# V3_nano.net
KiCad netlist of a schematic drawn in EAGLE
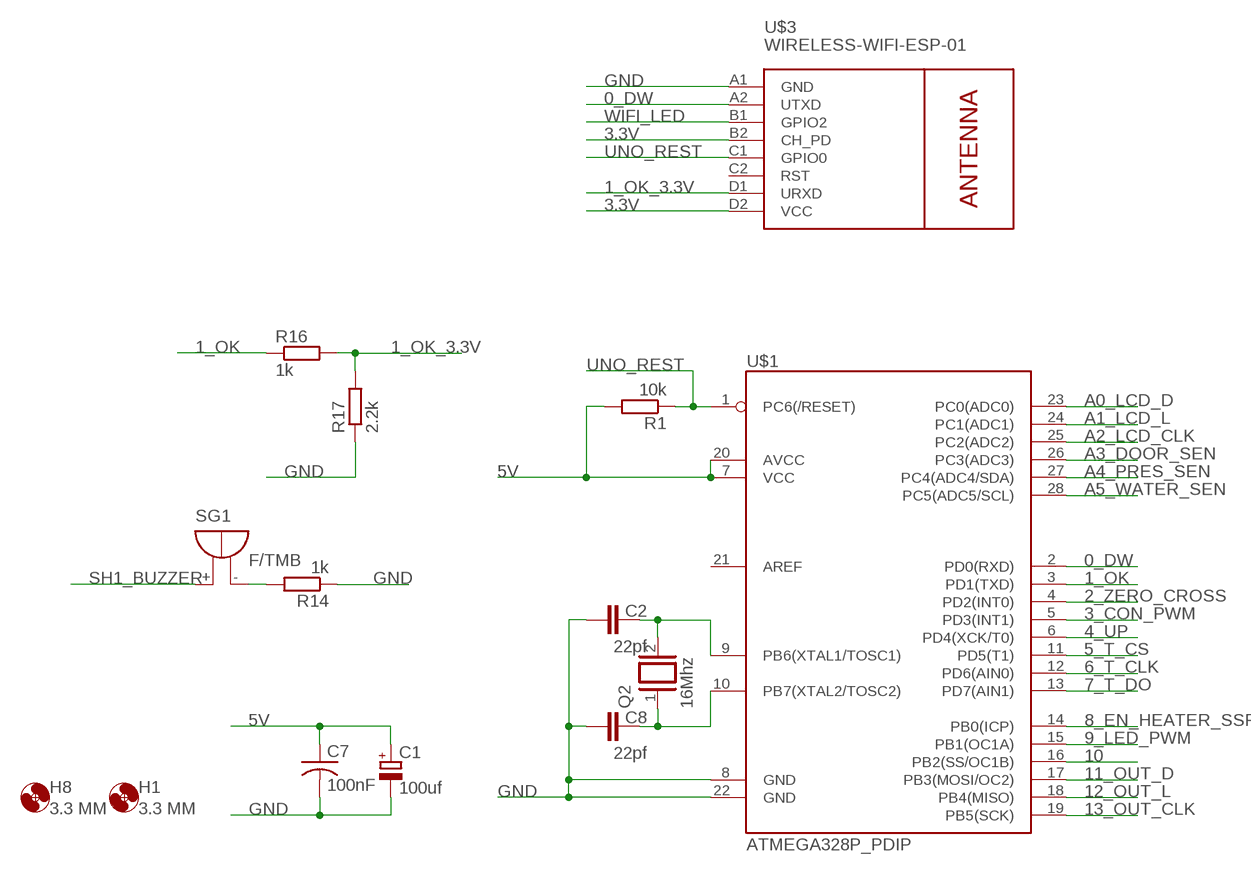
[diagram p0: schematic, sheet 1]
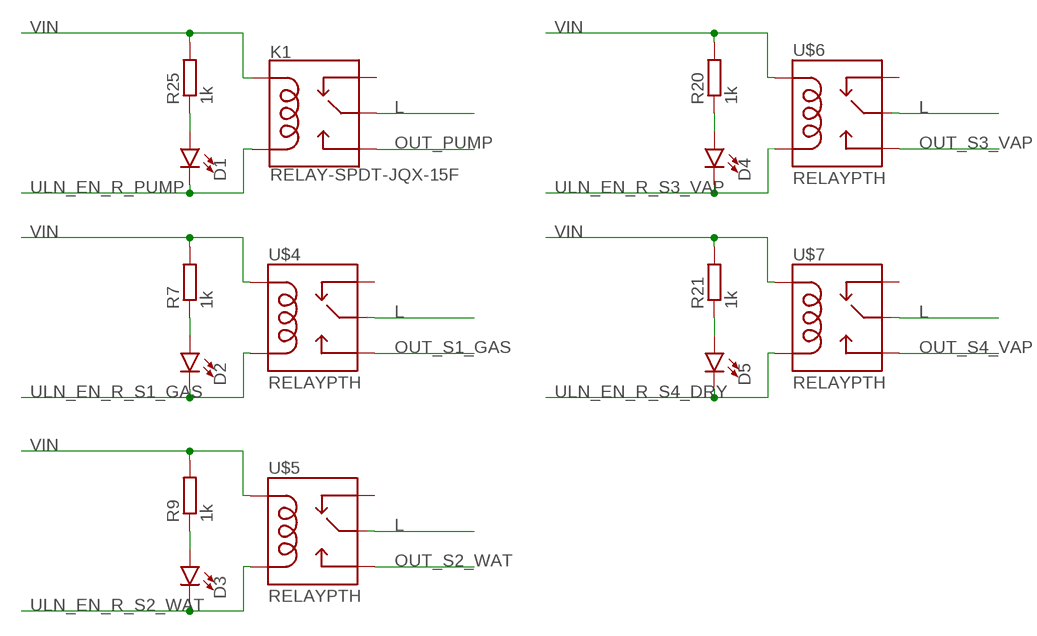
[diagram p1: schematic, sheet 2]
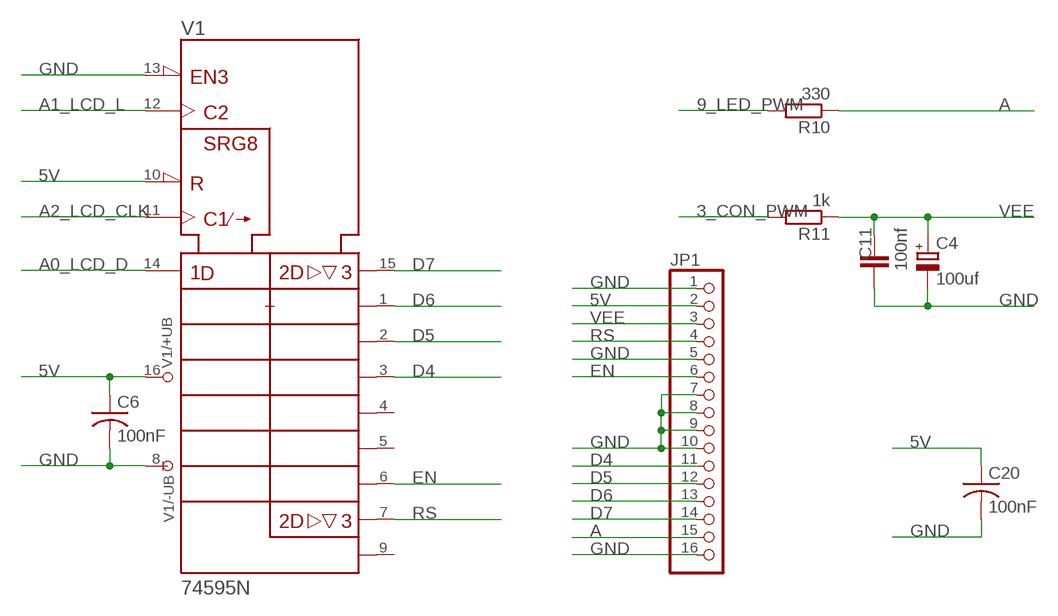
[diagram p2: schematic, sheet 3]
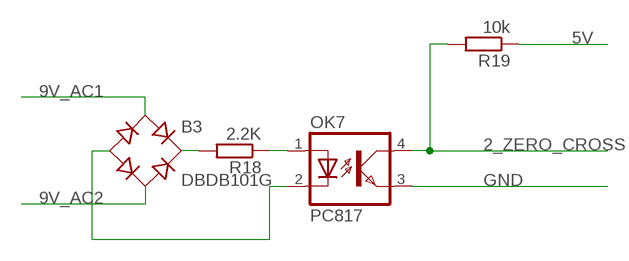
[diagram p3: schematic, sheet 4]
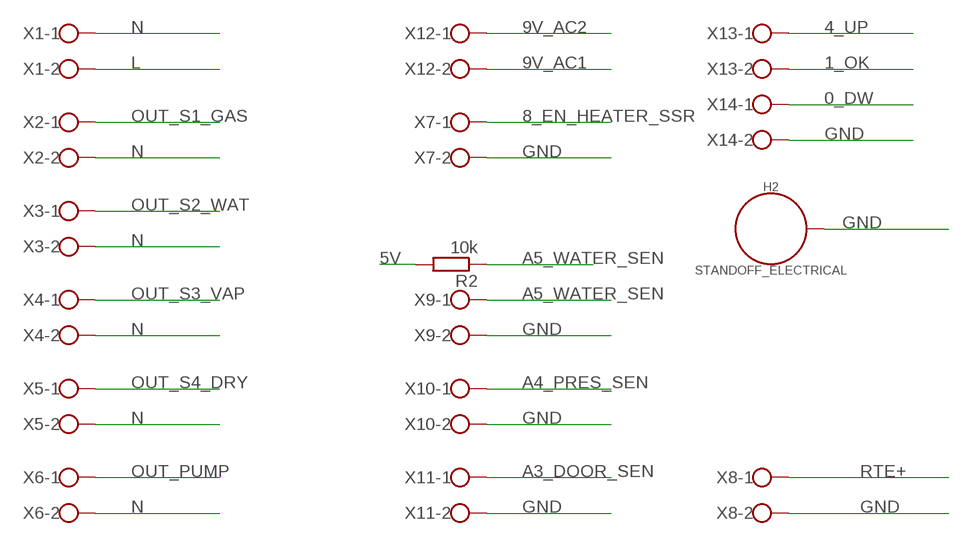
[diagram p4: schematic, sheet 5]
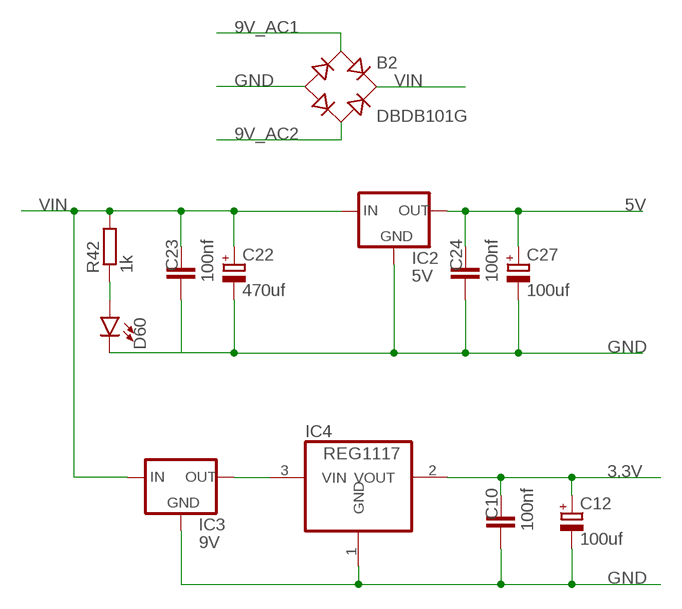
[diagram p5: schematic, sheet 6]
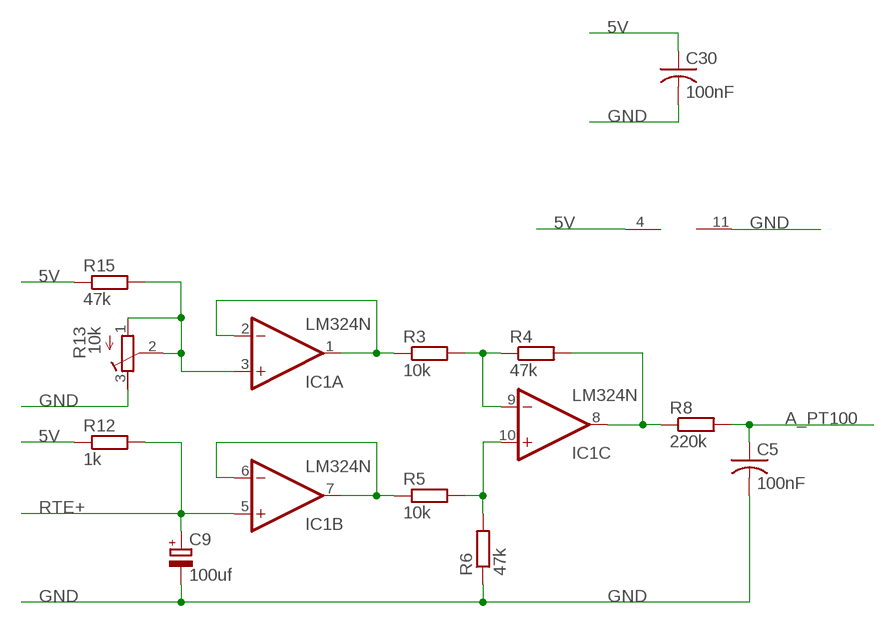
[diagram p6: schematic, sheet 7]
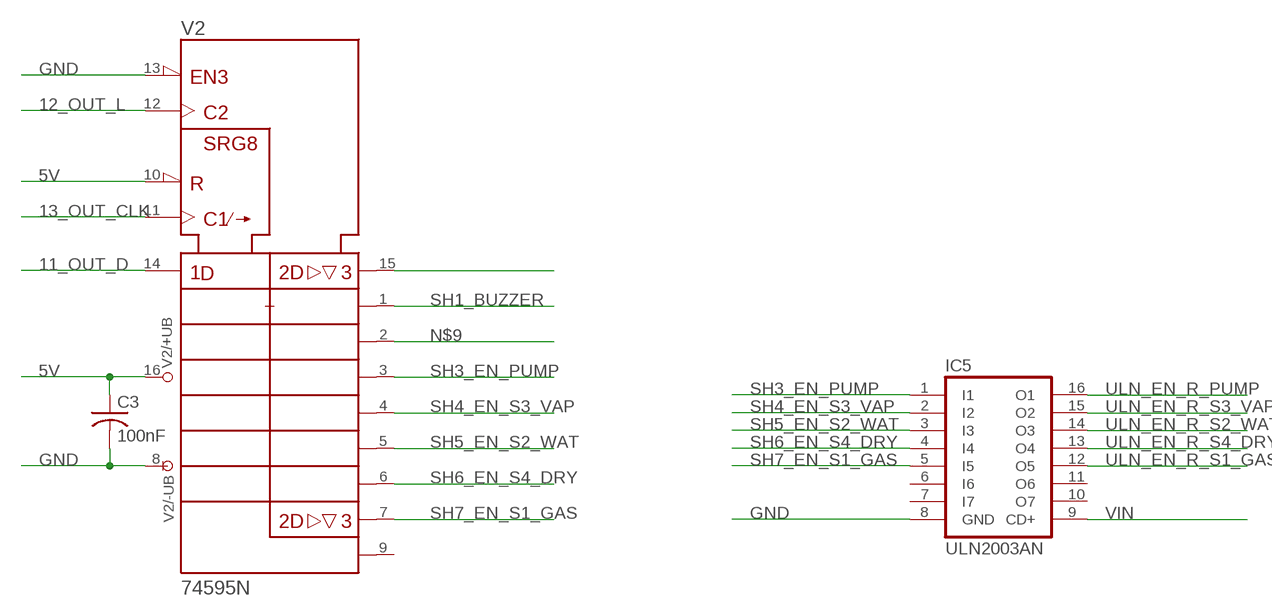
[diagram p7: schematic, sheet 8]

(export (version "E")
  (design (tool "Eeschema 10.0.6"))
  (components
    (comp (ref "B3")
      (value "DBDB101G")
      (footprint "eagle-import:DB")
      (libsource (lib "eagle-import") (part "DB?GDB101"))
    )
    (comp (ref "OK7")
      (value "PC817")
      (footprint "eagle-import:DIL04")
      (libsource (lib "eagle-import") (part "PC817"))
    )
    (comp (ref "R18")
      (value "2.2K")
      (footprint "eagle-import:0207_10")
      (libsource (lib "eagle-import") (part "R-EU_0207/10"))
    )
    (comp (ref "R19")
      (value "10k")
      (footprint "eagle-import:0207_10")
      (libsource (lib "eagle-import") (part "R-EU_0207/10"))
    )
    (comp (ref "H2")
      (value "STANDOFF_ELECTRICAL")
      (footprint "eagle-import:STANDOFF-ELECTRICAL")
      (libsource (lib "eagle-import") (part "STANDOFF_ELECTRICAL"))
    )
    (comp (ref "R2")
      (value "10k")
      (footprint "eagle-import:0207_10")
      (libsource (lib "eagle-import") (part "R-EU_0207/10"))
    )
    (comp (ref "X1")
      (value "W237-102")
      (footprint "eagle-import:W237-102")
      (fields (field (name "MPN") "237-102"))
      (libsource (lib "eagle-import") (part "W237-102"))
    )
    (comp (ref "X2")
      (value "W237-102")
      (footprint "eagle-import:W237-102")
      (fields (field (name "MPN") "237-102"))
      (libsource (lib "eagle-import") (part "W237-102"))
    )
    (comp (ref "X3")
      (value "W237-102")
      (footprint "eagle-import:W237-102")
      (fields (field (name "MPN") "237-102"))
      (libsource (lib "eagle-import") (part "W237-102"))
    )
    (comp (ref "X4")
      (value "W237-102")
      (footprint "eagle-import:W237-102")
      (fields (field (name "MPN") "237-102"))
      (libsource (lib "eagle-import") (part "W237-102"))
    )
    (comp (ref "X5")
      (value "W237-102")
      (footprint "eagle-import:W237-102")
      (fields (field (name "MPN") "237-102"))
      (libsource (lib "eagle-import") (part "W237-102"))
    )
    (comp (ref "X6")
      (value "W237-102")
      (footprint "eagle-import:W237-102")
      (fields (field (name "MPN") "237-102"))
      (libsource (lib "eagle-import") (part "W237-102"))
    )
    (comp (ref "X7")
      (value "W237-102")
      (footprint "eagle-import:W237-102")
      (fields (field (name "MPN") "237-102"))
      (libsource (lib "eagle-import") (part "W237-102"))
    )
    (comp (ref "X8")
      (value "W237-102")
      (footprint "eagle-import:W237-102")
      (fields (field (name "MPN") "237-102"))
      (libsource (lib "eagle-import") (part "W237-102"))
    )
    (comp (ref "X9")
      (value "W237-102")
      (footprint "eagle-import:W237-102")
      (fields (field (name "MPN") "237-102"))
      (libsource (lib "eagle-import") (part "W237-102"))
    )
    (comp (ref "X10")
      (value "W237-102")
      (footprint "eagle-import:W237-102")
      (fields (field (name "MPN") "237-102"))
      (libsource (lib "eagle-import") (part "W237-102"))
    )
    (comp (ref "X11")
      (value "W237-102")
      (footprint "eagle-import:W237-102")
      (fields (field (name "MPN") "237-102"))
      (libsource (lib "eagle-import") (part "W237-102"))
    )
    (comp (ref "X12")
      (value "W237-102")
      (footprint "eagle-import:W237-102")
      (fields (field (name "MPN") "237-102"))
      (libsource (lib "eagle-import") (part "W237-102"))
    )
    (comp (ref "X13")
      (value "W237-102")
      (footprint "eagle-import:W237-102")
      (fields (field (name "MPN") "237-102"))
      (libsource (lib "eagle-import") (part "W237-102"))
    )
    (comp (ref "X14")
      (value "W237-102")
      (footprint "eagle-import:W237-102")
      (fields (field (name "MPN") "237-102"))
      (libsource (lib "eagle-import") (part "W237-102"))
    )
    (comp (ref "C5")
      (value "100nF")
      (footprint "eagle-import:C050-035X075")
      (libsource (lib "eagle-import") (part "C-US050-035X075"))
    )
    (comp (ref "C9")
      (value "100uf")
      (footprint "eagle-import:E3,5-8")
      (libsource (lib "eagle-import") (part "CPOL-EUE3.5-8"))
    )
    (comp (ref "C30")
      (value "100nF")
      (footprint "eagle-import:C050-035X075")
      (libsource (lib "eagle-import") (part "C-US050-035X075"))
    )
    (comp (ref "IC1")
      (value "LM324N")
      (footprint "eagle-import:DIL14")
      (libsource (lib "eagle-import") (part "LM324N"))
    )
    (comp (ref "R3")
      (value "10k")
      (footprint "eagle-import:0207_10")
      (libsource (lib "eagle-import") (part "R-EU_0207/10"))
    )
    (comp (ref "R4")
      (value "47k")
      (footprint "eagle-import:0207_10")
      (libsource (lib "eagle-import") (part "R-EU_0207/10"))
    )
    (comp (ref "R5")
      (value "10k")
      (footprint "eagle-import:0207_10")
      (libsource (lib "eagle-import") (part "R-EU_0207/10"))
    )
    (comp (ref "R6")
      (value "47k")
      (footprint "eagle-import:0207_10")
      (libsource (lib "eagle-import") (part "R-EU_0207/10"))
    )
    (comp (ref "R8")
      (value "220k")
      (footprint "eagle-import:0207_10")
      (libsource (lib "eagle-import") (part "R-EU_0207/10"))
    )
    (comp (ref "R12")
      (value "1k")
      (footprint "eagle-import:0207_10")
      (libsource (lib "eagle-import") (part "R-EU_0207/10"))
    )
    (comp (ref "R13")
      (value "10k")
      (footprint "eagle-import:RTRIM64W")
      (libsource (lib "eagle-import") (part "R-TRIMM64W"))
    )
    (comp (ref "R15")
      (value "47k")
      (footprint "eagle-import:0207_10")
      (libsource (lib "eagle-import") (part "R-EU_0207/10"))
    )
    (comp (ref "D1")
      (value "LED5MM")
      (footprint "eagle-import:LED_5MM")
      (libsource (lib "eagle-import") (part "LED5MM"))
    )
    (comp (ref "D2")
      (value "LED5MM")
      (footprint "eagle-import:LED_5MM")
      (libsource (lib "eagle-import") (part "LED5MM"))
    )
    (comp (ref "D3")
      (value "LED5MM")
      (footprint "eagle-import:LED_5MM")
      (libsource (lib "eagle-import") (part "LED5MM"))
    )
    (comp (ref "D4")
      (value "LED5MM")
      (footprint "eagle-import:LED_5MM")
      (libsource (lib "eagle-import") (part "LED5MM"))
    )
    (comp (ref "D5")
      (value "LED5MM")
      (footprint "eagle-import:LED_5MM")
      (libsource (lib "eagle-import") (part "LED5MM"))
    )
    (comp (ref "K1")
      (value "RELAY-SPDT-JQX-15F")
      (footprint "eagle-import:RELAY-T90")
      (libsource (lib "eagle-import") (part "RELAY-SPDT-JQX-15F"))
    )
    (comp (ref "R7")
      (value "1k")
      (footprint "eagle-import:0207_10")
      (libsource (lib "eagle-import") (part "R-EU_0207/10"))
    )
    (comp (ref "R9")
      (value "1k")
      (footprint "eagle-import:0207_10")
      (libsource (lib "eagle-import") (part "R-EU_0207/10"))
    )
    (comp (ref "R20")
      (value "1k")
      (footprint "eagle-import:0207_10")
      (libsource (lib "eagle-import") (part "R-EU_0207/10"))
    )
    (comp (ref "R21")
      (value "1k")
      (footprint "eagle-import:0207_10")
      (libsource (lib "eagle-import") (part "R-EU_0207/10"))
    )
    (comp (ref "R25")
      (value "1k")
      (footprint "eagle-import:0207_10")
      (libsource (lib "eagle-import") (part "R-EU_0207/10"))
    )
    (comp (ref "U$4")
      (value "RELAYPTH")
      (footprint "eagle-import:SRD-05VDC-SL-C")
      (libsource (lib "eagle-import") (part "RELAYPTH"))
    )
    (comp (ref "U$5")
      (value "RELAYPTH")
      (footprint "eagle-import:SRD-05VDC-SL-C")
      (libsource (lib "eagle-import") (part "RELAYPTH"))
    )
    (comp (ref "U$6")
      (value "RELAYPTH")
      (footprint "eagle-import:SRD-05VDC-SL-C")
      (libsource (lib "eagle-import") (part "RELAYPTH"))
    )
    (comp (ref "U$7")
      (value "RELAYPTH")
      (footprint "eagle-import:SRD-05VDC-SL-C")
      (libsource (lib "eagle-import") (part "RELAYPTH"))
    )
    (comp (ref "C4")
      (value "100uf")
      (footprint "eagle-import:E3,5-8")
      (libsource (lib "eagle-import") (part "CPOL-EUE3.5-8"))
    )
    (comp (ref "C6")
      (value "100nF")
      (footprint "eagle-import:C050-035X075")
      (libsource (lib "eagle-import") (part "C-US050-035X075"))
    )
    (comp (ref "C11")
      (value "100nf")
      (footprint "eagle-import:C050-030X075")
      (libsource (lib "eagle-import") (part "C-EU050-030X075"))
    )
    (comp (ref "C20")
      (value "100nF")
      (footprint "eagle-import:C050-035X075")
      (libsource (lib "eagle-import") (part "C-US050-035X075"))
    )
    (comp (ref "JP1")
      (value "PINHD-1X16")
      (footprint "eagle-import:1X16")
      (libsource (lib "eagle-import") (part "PINHD-1X16"))
    )
    (comp (ref "R10")
      (value "330")
      (footprint "eagle-import:0207_10")
      (libsource (lib "eagle-import") (part "R-EU_0207/10"))
    )
    (comp (ref "R11")
      (value "1k")
      (footprint "eagle-import:0207_10")
      (libsource (lib "eagle-import") (part "R-EU_0207/10"))
    )
    (comp (ref "V1")
      (value "74595N")
      (footprint "eagle-import:DIL16")
      (libsource (lib "eagle-import") (part "74595N"))
    )
    (comp (ref "C3")
      (value "100nF")
      (footprint "eagle-import:C050-035X075")
      (libsource (lib "eagle-import") (part "C-US050-035X075"))
    )
    (comp (ref "IC5")
      (value "ULN2003AN")
      (footprint "eagle-import:DIL16")
      (libsource (lib "eagle-import") (part "ULN2003AN"))
    )
    (comp (ref "V2")
      (value "74595N")
      (footprint "eagle-import:DIL16")
      (libsource (lib "eagle-import") (part "74595N"))
    )
    (comp (ref "B2")
      (value "DBDB101G")
      (footprint "eagle-import:DB")
      (libsource (lib "eagle-import") (part "DB?GDB101"))
    )
    (comp (ref "C10")
      (value "100nf")
      (footprint "eagle-import:C050-030X075")
      (libsource (lib "eagle-import") (part "C-EU050-030X075"))
    )
    (comp (ref "C12")
      (value "100uf")
      (footprint "eagle-import:E3,5-8")
      (libsource (lib "eagle-import") (part "CPOL-EUE3.5-8"))
    )
    (comp (ref "C22")
      (value "470uf")
      (footprint "eagle-import:E3,5-8")
      (libsource (lib "eagle-import") (part "CPOL-EUE3.5-8"))
    )
    (comp (ref "C23")
      (value "100nf")
      (footprint "eagle-import:C050-030X075")
      (libsource (lib "eagle-import") (part "C-EU050-030X075"))
    )
    (comp (ref "C24")
      (value "100nf")
      (footprint "eagle-import:C050-030X075")
      (libsource (lib "eagle-import") (part "C-EU050-030X075"))
    )
    (comp (ref "C27")
      (value "100uf")
      (footprint "eagle-import:E3,5-8")
      (libsource (lib "eagle-import") (part "CPOL-EUE3.5-8"))
    )
    (comp (ref "D60")
      (value "LED5MM")
      (footprint "eagle-import:LED_5MM")
      (libsource (lib "eagle-import") (part "LED5MM"))
    )
    (comp (ref "IC2")
      (value "5V")
      (footprint "eagle-import:78XXL")
      (libsource (lib "eagle-import") (part "V_REG_78XXSIDE"))
    )
    (comp (ref "IC3")
      (value "9V")
      (footprint "eagle-import:78XXL")
      (libsource (lib "eagle-import") (part "V_REG_78XXSIDE"))
    )
    (comp (ref "IC4")
      (value "REG1117")
      (footprint "eagle-import:SOT223")
      (libsource (lib "eagle-import") (part "REG1117"))
    )
    (comp (ref "R42")
      (value "1k")
      (footprint "eagle-import:0207_10")
      (libsource (lib "eagle-import") (part "R-EU_0207/10"))
    )
    (comp (ref "C1")
      (value "100uf")
      (footprint "eagle-import:E3,5-8")
      (libsource (lib "eagle-import") (part "CPOL-EUE3.5-8"))
    )
    (comp (ref "C2")
      (value "22pf")
      (footprint "eagle-import:C050-030X075")
      (libsource (lib "eagle-import") (part "C-EU050-030X075"))
    )
    (comp (ref "C7")
      (value "100nF")
      (footprint "eagle-import:C050-035X075")
      (libsource (lib "eagle-import") (part "C-US050-035X075"))
    )
    (comp (ref "C8")
      (value "22pf")
      (footprint "eagle-import:C050-030X075")
      (libsource (lib "eagle-import") (part "C-EU050-030X075"))
    )
    (comp (ref "H1")
      (value "3.3 MM")
      (footprint "eagle-import:3,3")
      (libsource (lib "eagle-import") (part "MOUNT-HOLE3.3"))
    )
    (comp (ref "H8")
      (value "3.3 MM")
      (footprint "eagle-import:3,3")
      (libsource (lib "eagle-import") (part "MOUNT-HOLE3.3"))
    )
    (comp (ref "Q2")
      (value "16Mhz")
      (footprint "eagle-import:QS")
      (libsource (lib "eagle-import") (part "XTAL/S"))
    )
    (comp (ref "R1")
      (value "10k")
      (footprint "eagle-import:0207_10")
      (libsource (lib "eagle-import") (part "R-EU_0207/10"))
    )
    (comp (ref "R14")
      (value "1k")
      (footprint "eagle-import:0207_10")
      (libsource (lib "eagle-import") (part "R-EU_0207/10"))
    )
    (comp (ref "R16")
      (value "1k")
      (footprint "eagle-import:0207_10")
      (libsource (lib "eagle-import") (part "R-EU_0207/10"))
    )
    (comp (ref "R17")
      (value "2.2k")
      (footprint "eagle-import:0207_10")
      (libsource (lib "eagle-import") (part "R-EU_0207/10"))
    )
    (comp (ref "SG1")
      (value "F/TMB")
      (footprint "eagle-import:F_TMB")
      (libsource (lib "eagle-import") (part "F/TMB"))
    )
    (comp (ref "U$1")
      (value "ATMEGA328P_PDIP")
      (footprint "eagle-import:DIL-28-3")
      (libsource (lib "eagle-import") (part "ATMEGA328P_PDIP"))
    )
    (comp (ref "U$3")
      (value "WIRELESS-WIFI-ESP-01")
      (footprint "eagle-import:WIRELESS-WIFI-ESP-01")
      (libsource (lib "eagle-import") (part "WIRELESS-WIFI-ESP-01"))
    )
  )
  (nets
    (net (code "1") (name "0_DW") (class "Default")
      (node (ref "U$1") (pin "2") (pinfunction "PD0(RXD)_2") (pintype "bidirectional"))
      (node (ref "U$3") (pin "A2") (pinfunction "UTXD_A2") (pintype "bidirectional"))
      (node (ref "X14") (pin "1") (pinfunction "KL_1") (pintype "passive"))
    )
    (net (code "2") (name "1_OK") (class "Default")
      (node (ref "R16") (pin "1") (pinfunction "1_1") (pintype "passive"))
      (node (ref "U$1") (pin "3") (pinfunction "PD1(TXD)_3") (pintype "bidirectional"))
      (node (ref "X13") (pin "2") (pinfunction "KL_2") (pintype "passive"))
    )
    (net (code "3") (name "1_OK_3.3V") (class "Default")
      (node (ref "R16") (pin "2") (pinfunction "2_2") (pintype "passive"))
      (node (ref "R17") (pin "2") (pinfunction "2_2") (pintype "passive"))
      (node (ref "U$3") (pin "D1") (pinfunction "URXD_D1") (pintype "bidirectional"))
    )
    (net (code "4") (name "2_ZERO_CROSS") (class "Default")
      (node (ref "OK7") (pin "4") (pinfunction "COL_4") (pintype "passive"))
      (node (ref "R19") (pin "2") (pinfunction "2_2") (pintype "passive"))
      (node (ref "U$1") (pin "4") (pinfunction "PD2(INT0)_4") (pintype "bidirectional"))
    )
    (net (code "5") (name "3.3V") (class "Default")
      (node (ref "C10") (pin "2") (pinfunction "2_2") (pintype "passive"))
      (node (ref "C12") (pin "+") (pinfunction "+_+") (pintype "passive"))
      (node (ref "IC4") (pin "2") (pinfunction "VOUT_2") (pintype "output"))
      (node (ref "U$3") (pin "B2") (pinfunction "CH_PD_B2") (pintype "bidirectional"))
      (node (ref "U$3") (pin "D2") (pinfunction "VCC_D2") (pintype "power_in"))
    )
    (net (code "6") (name "3_CON_PWM") (class "Default")
      (node (ref "R11") (pin "2") (pinfunction "2_2") (pintype "passive"))
      (node (ref "U$1") (pin "5") (pinfunction "PD3(INT1)_5") (pintype "bidirectional"))
    )
    (net (code "7") (name "4_UP") (class "Default")
      (node (ref "U$1") (pin "6") (pinfunction "PD4(XCK/T0)_6") (pintype "bidirectional"))
      (node (ref "X13") (pin "1") (pinfunction "KL_1") (pintype "passive"))
    )
    (net (code "8") (name "5V") (class "Default")
      (node (ref "C1") (pin "+") (pinfunction "+_+") (pintype "passive"))
      (node (ref "C20") (pin "1") (pinfunction "1_1") (pintype "passive"))
      (node (ref "C24") (pin "2") (pinfunction "2_2") (pintype "passive"))
      (node (ref "C27") (pin "+") (pinfunction "+_+") (pintype "passive"))
      (node (ref "C3") (pin "1") (pinfunction "1_1") (pintype "passive"))
      (node (ref "C30") (pin "1") (pinfunction "1_1") (pintype "passive"))
      (node (ref "C6") (pin "1") (pinfunction "1_1") (pintype "passive"))
      (node (ref "C7") (pin "1") (pinfunction "1_1") (pintype "passive"))
      (node (ref "IC1") (pin "4") (pinfunction "V+_4") (pintype "power_in"))
      (node (ref "IC2") (pin "OUT") (pinfunction "OUT_OUT") (pintype "output"))
      (node (ref "JP1") (pin "2") (pinfunction "2_2") (pintype "passive"))
      (node (ref "R1") (pin "2") (pinfunction "2_2") (pintype "passive"))
      (node (ref "R12") (pin "1") (pinfunction "1_1") (pintype "passive"))
      (node (ref "R15") (pin "1") (pinfunction "1_1") (pintype "passive"))
      (node (ref "R19") (pin "1") (pinfunction "1_1") (pintype "passive"))
      (node (ref "R2") (pin "2") (pinfunction "2_2") (pintype "passive"))
      (node (ref "U$1") (pin "20") (pinfunction "AVCC_20") (pintype "bidirectional"))
      (node (ref "U$1") (pin "7") (pinfunction "VCC_7") (pintype "bidirectional"))
      (node (ref "V1") (pin "10") (pinfunction "~{SRCLR}_10") (pintype "input"))
      (node (ref "V1") (pin "16") (pinfunction "+UB_16") (pintype "power_in"))
      (node (ref "V2") (pin "10") (pinfunction "~{SRCLR}_10") (pintype "input"))
      (node (ref "V2") (pin "16") (pinfunction "+UB_16") (pintype "power_in"))
    )
    (net (code "9") (name "5_T_CS") (class "Default")
      (node (ref "U$1") (pin "11") (pinfunction "PD5(T1)_11") (pintype "bidirectional"))
    )
    (net (code "10") (name "6_T_CLK") (class "Default")
      (node (ref "U$1") (pin "12") (pinfunction "PD6(AIN0)_12") (pintype "bidirectional"))
    )
    (net (code "11") (name "7_T_DO") (class "Default")
      (node (ref "U$1") (pin "13") (pinfunction "PD7(AIN1)_13") (pintype "bidirectional"))
    )
    (net (code "12") (name "8_EN_HEATER_SSR") (class "Default")
      (node (ref "U$1") (pin "14") (pinfunction "PB0(ICP)_14") (pintype "bidirectional"))
      (node (ref "X7") (pin "1") (pinfunction "KL_1") (pintype "passive"))
    )
    (net (code "13") (name "9V_AC1") (class "Default")
      (node (ref "B2") (pin "AC1") (pinfunction "AC1_AC1") (pintype "passive"))
      (node (ref "B3") (pin "AC1") (pinfunction "AC1_AC1") (pintype "passive"))
      (node (ref "X12") (pin "2") (pinfunction "KL_2") (pintype "passive"))
    )
    (net (code "14") (name "9V_AC2") (class "Default")
      (node (ref "B2") (pin "AC2") (pinfunction "AC2_AC2") (pintype "passive"))
      (node (ref "B3") (pin "AC2") (pinfunction "AC2_AC2") (pintype "passive"))
      (node (ref "X12") (pin "1") (pinfunction "KL_1") (pintype "passive"))
    )
    (net (code "15") (name "9_LED_PWM") (class "Default")
      (node (ref "R10") (pin "2") (pinfunction "2_2") (pintype "passive"))
      (node (ref "U$1") (pin "15") (pinfunction "PB1(OC1A)_15") (pintype "bidirectional"))
    )
    (net (code "16") (name "10") (class "Default")
      (node (ref "U$1") (pin "16") (pinfunction "PB2(SS/OC1B)_16") (pintype "bidirectional"))
    )
    (net (code "17") (name "11_OUT_D") (class "Default")
      (node (ref "U$1") (pin "17") (pinfunction "PB3(MOSI/OC2)_17") (pintype "bidirectional"))
      (node (ref "V2") (pin "14") (pinfunction "SER_14") (pintype "input"))
    )
    (net (code "18") (name "12_OUT_L") (class "Default")
      (node (ref "U$1") (pin "18") (pinfunction "PB4(MISO)_18") (pintype "bidirectional"))
      (node (ref "V2") (pin "12") (pinfunction "RCK_12") (pintype "input"))
    )
    (net (code "19") (name "13_OUT_CLK") (class "Default")
      (node (ref "U$1") (pin "19") (pinfunction "PB5(SCK)_19") (pintype "bidirectional"))
      (node (ref "V2") (pin "11") (pinfunction "SRCK_11") (pintype "input"))
    )
    (net (code "20") (name "A") (class "Default")
      (node (ref "JP1") (pin "15") (pinfunction "15_15") (pintype "passive"))
      (node (ref "R10") (pin "1") (pinfunction "1_1") (pintype "passive"))
    )
    (net (code "21") (name "A0_LCD_D") (class "Default")
      (node (ref "U$1") (pin "23") (pinfunction "PC0(ADC0)_23") (pintype "bidirectional"))
      (node (ref "V1") (pin "14") (pinfunction "SER_14") (pintype "input"))
    )
    (net (code "22") (name "A1_LCD_L") (class "Default")
      (node (ref "U$1") (pin "24") (pinfunction "PC1(ADC1)_24") (pintype "bidirectional"))
      (node (ref "V1") (pin "12") (pinfunction "RCK_12") (pintype "input"))
    )
    (net (code "23") (name "A2_LCD_CLK") (class "Default")
      (node (ref "U$1") (pin "25") (pinfunction "PC2(ADC2)_25") (pintype "bidirectional"))
      (node (ref "V1") (pin "11") (pinfunction "SRCK_11") (pintype "input"))
    )
    (net (code "24") (name "A3_DOOR_SEN") (class "Default")
      (node (ref "U$1") (pin "26") (pinfunction "PC3(ADC3)_26") (pintype "bidirectional"))
      (node (ref "X11") (pin "1") (pinfunction "KL_1") (pintype "passive"))
    )
    (net (code "25") (name "A4_PRES_SEN") (class "Default")
      (node (ref "U$1") (pin "27") (pinfunction "PC4(ADC4/SDA)_27") (pintype "bidirectional"))
      (node (ref "X10") (pin "1") (pinfunction "KL_1") (pintype "passive"))
    )
    (net (code "26") (name "A5_WATER_SEN") (class "Default")
      (node (ref "R2") (pin "1") (pinfunction "1_1") (pintype "passive"))
      (node (ref "U$1") (pin "28") (pinfunction "PC5(ADC5/SCL)_28") (pintype "bidirectional"))
      (node (ref "X9") (pin "1") (pinfunction "KL_1") (pintype "passive"))
    )
    (net (code "27") (name "A_PT100") (class "Default")
      (node (ref "C5") (pin "1") (pinfunction "1_1") (pintype "passive"))
      (node (ref "R8") (pin "2") (pinfunction "2_2") (pintype "passive"))
    )
    (net (code "28") (name "D4") (class "Default")
      (node (ref "JP1") (pin "11") (pinfunction "11_11") (pintype "passive"))
      (node (ref "V1") (pin "3") (pinfunction "QD_3") (pintype "tri_state"))
    )
    (net (code "29") (name "D5") (class "Default")
      (node (ref "JP1") (pin "12") (pinfunction "12_12") (pintype "passive"))
      (node (ref "V1") (pin "2") (pinfunction "QC_2") (pintype "tri_state"))
    )
    (net (code "30") (name "D6") (class "Default")
      (node (ref "JP1") (pin "13") (pinfunction "13_13") (pintype "passive"))
      (node (ref "V1") (pin "1") (pinfunction "QB_1") (pintype "tri_state"))
    )
    (net (code "31") (name "D7") (class "Default")
      (node (ref "JP1") (pin "14") (pinfunction "14_14") (pintype "passive"))
      (node (ref "V1") (pin "15") (pinfunction "QA_15") (pintype "tri_state"))
    )
    (net (code "32") (name "EN") (class "Default")
      (node (ref "JP1") (pin "6") (pinfunction "6_6") (pintype "passive"))
      (node (ref "V1") (pin "6") (pinfunction "QG_6") (pintype "tri_state"))
    )
    (net (code "33") (name "GND") (class "Default")
      (node (ref "B2") (pin "-") (pinfunction "-_-") (pintype "passive"))
      (node (ref "C1") (pin "-") (pinfunction "-_-") (pintype "passive"))
      (node (ref "C10") (pin "1") (pinfunction "1_1") (pintype "passive"))
      (node (ref "C11") (pin "1") (pinfunction "1_1") (pintype "passive"))
      (node (ref "C12") (pin "-") (pinfunction "-_-") (pintype "passive"))
      (node (ref "C2") (pin "1") (pinfunction "1_1") (pintype "passive"))
      (node (ref "C20") (pin "2") (pinfunction "2_2") (pintype "passive"))
      (node (ref "C22") (pin "-") (pinfunction "-_-") (pintype "passive"))
      (node (ref "C23") (pin "1") (pinfunction "1_1") (pintype "passive"))
      (node (ref "C24") (pin "1") (pinfunction "1_1") (pintype "passive"))
      (node (ref "C27") (pin "-") (pinfunction "-_-") (pintype "passive"))
      (node (ref "C3") (pin "2") (pinfunction "2_2") (pintype "passive"))
      (node (ref "C30") (pin "2") (pinfunction "2_2") (pintype "passive"))
      (node (ref "C4") (pin "-") (pinfunction "-_-") (pintype "passive"))
      (node (ref "C5") (pin "2") (pinfunction "2_2") (pintype "passive"))
      (node (ref "C6") (pin "2") (pinfunction "2_2") (pintype "passive"))
      (node (ref "C7") (pin "2") (pinfunction "2_2") (pintype "passive"))
      (node (ref "C8") (pin "1") (pinfunction "1_1") (pintype "passive"))
      (node (ref "C9") (pin "-") (pinfunction "-_-") (pintype "passive"))
      (node (ref "D60") (pin "K") (pinfunction "C_K") (pintype "passive"))
      (node (ref "H2") (pin "P1") (pinfunction "P$1_P1") (pintype "bidirectional"))
      (node (ref "IC1") (pin "11") (pinfunction "V-_11") (pintype "power_in"))
      (node (ref "IC2") (pin "GND") (pinfunction "GND_GND") (pintype "input"))
      (node (ref "IC3") (pin "GND") (pinfunction "GND_GND") (pintype "input"))
      (node (ref "IC4") (pin "1") (pinfunction "GND_1") (pintype "power_in"))
      (node (ref "IC5") (pin "8") (pinfunction "GND_8") (pintype "power_in"))
      (node (ref "JP1") (pin "1") (pinfunction "1_1") (pintype "passive"))
      (node (ref "JP1") (pin "10") (pinfunction "10_10") (pintype "passive"))
      (node (ref "JP1") (pin "16") (pinfunction "16_16") (pintype "passive"))
      (node (ref "JP1") (pin "5") (pinfunction "5_5") (pintype "passive"))
      (node (ref "JP1") (pin "7") (pinfunction "7_7") (pintype "passive"))
      (node (ref "JP1") (pin "8") (pinfunction "8_8") (pintype "passive"))
      (node (ref "JP1") (pin "9") (pinfunction "9_9") (pintype "passive"))
      (node (ref "OK7") (pin "3") (pinfunction "EMIT_3") (pintype "passive"))
      (node (ref "R13") (pin "3") (pinfunction "E_3") (pintype "passive"))
      (node (ref "R14") (pin "1") (pinfunction "1_1") (pintype "passive"))
      (node (ref "R17") (pin "1") (pinfunction "1_1") (pintype "passive"))
      (node (ref "R6") (pin "1") (pinfunction "1_1") (pintype "passive"))
      (node (ref "U$1") (pin "22") (pinfunction "GND_22") (pintype "bidirectional"))
      (node (ref "U$1") (pin "8") (pinfunction "GND_8") (pintype "bidirectional"))
      (node (ref "U$3") (pin "A1") (pinfunction "GND_A1") (pintype "power_in"))
      (node (ref "V1") (pin "13") (pinfunction "~{G}_13") (pintype "input"))
      (node (ref "V1") (pin "8") (pinfunction "-UB_8") (pintype "power_in"))
      (node (ref "V2") (pin "13") (pinfunction "~{G}_13") (pintype "input"))
      (node (ref "V2") (pin "8") (pinfunction "-UB_8") (pintype "power_in"))
      (node (ref "X10") (pin "2") (pinfunction "KL_2") (pintype "passive"))
      (node (ref "X11") (pin "2") (pinfunction "KL_2") (pintype "passive"))
      (node (ref "X14") (pin "2") (pinfunction "KL_2") (pintype "passive"))
      (node (ref "X7") (pin "2") (pinfunction "KL_2") (pintype "passive"))
      (node (ref "X8") (pin "2") (pinfunction "KL_2") (pintype "passive"))
      (node (ref "X9") (pin "2") (pinfunction "KL_2") (pintype "passive"))
    )
    (net (code "34") (name "L") (class "Default")
      (node (ref "K1") (pin "MAIN") (pinfunction "MAIN_MAIN") (pintype "bidirectional"))
      (node (ref "U$4") (pin "SWCOMMON") (pinfunction "SWCOMMON_SWCOMMON") (pintype "bidirectional"))
      (node (ref "U$5") (pin "SWCOMMON") (pinfunction "SWCOMMON_SWCOMMON") (pintype "bidirectional"))
      (node (ref "U$6") (pin "SWCOMMON") (pinfunction "SWCOMMON_SWCOMMON") (pintype "bidirectional"))
      (node (ref "U$7") (pin "SWCOMMON") (pinfunction "SWCOMMON_SWCOMMON") (pintype "bidirectional"))
      (node (ref "X1") (pin "2") (pinfunction "KL_2") (pintype "passive"))
    )
    (net (code "35") (name "N") (class "Default")
      (node (ref "X1") (pin "1") (pinfunction "KL_1") (pintype "passive"))
      (node (ref "X2") (pin "2") (pinfunction "KL_2") (pintype "passive"))
      (node (ref "X3") (pin "2") (pinfunction "KL_2") (pintype "passive"))
      (node (ref "X4") (pin "2") (pinfunction "KL_2") (pintype "passive"))
      (node (ref "X5") (pin "2") (pinfunction "KL_2") (pintype "passive"))
      (node (ref "X6") (pin "2") (pinfunction "KL_2") (pintype "passive"))
    )
    (net (code "36") (name "N$9") (class "Default")
      (node (ref "V2") (pin "2") (pinfunction "QC_2") (pintype "tri_state"))
    )
    (net (code "37") (name "Net-(B3-Pad+)") (class "Default")
      (node (ref "B3") (pin "+") (pinfunction "+_+") (pintype "passive"))
      (node (ref "R18") (pin "2") (pinfunction "2_2") (pintype "passive"))
    )
    (net (code "38") (name "Net-(D1-PadA)") (class "Default")
      (node (ref "D1") (pin "A") (pinfunction "A_A") (pintype "passive"))
      (node (ref "R25") (pin "1") (pinfunction "1_1") (pintype "passive"))
    )
    (net (code "39") (name "Net-(D2-PadA)") (class "Default")
      (node (ref "D2") (pin "A") (pinfunction "A_A") (pintype "passive"))
      (node (ref "R7") (pin "1") (pinfunction "1_1") (pintype "passive"))
    )
    (net (code "40") (name "Net-(D3-PadA)") (class "Default")
      (node (ref "D3") (pin "A") (pinfunction "A_A") (pintype "passive"))
      (node (ref "R9") (pin "1") (pinfunction "1_1") (pintype "passive"))
    )
    (net (code "41") (name "Net-(D4-PadA)") (class "Default")
      (node (ref "D4") (pin "A") (pinfunction "A_A") (pintype "passive"))
      (node (ref "R20") (pin "1") (pinfunction "1_1") (pintype "passive"))
    )
    (net (code "42") (name "Net-(D5-PadA)") (class "Default")
      (node (ref "D5") (pin "A") (pinfunction "A_A") (pintype "passive"))
      (node (ref "R21") (pin "1") (pinfunction "1_1") (pintype "passive"))
    )
    (net (code "43") (name "Net-(D60-PadA)") (class "Default")
      (node (ref "D60") (pin "A") (pinfunction "A_A") (pintype "passive"))
      (node (ref "R42") (pin "1") (pinfunction "1_1") (pintype "passive"))
    )
    (net (code "44") (name "Net-(IC1A-+IN)") (class "Default")
      (node (ref "IC1") (pin "3") (pinfunction "+IN_3") (pintype "input"))
      (node (ref "R13") (pin "1") (pinfunction "A_1") (pintype "passive"))
      (node (ref "R13") (pin "2") (pinfunction "S_2") (pintype "passive"))
      (node (ref "R15") (pin "2") (pinfunction "2_2") (pintype "passive"))
    )
    (net (code "45") (name "Net-(IC1A--IN)") (class "Default")
      (node (ref "IC1") (pin "1") (pinfunction "OUT_1") (pintype "output"))
      (node (ref "IC1") (pin "2") (pinfunction "-IN_2") (pintype "input"))
      (node (ref "R3") (pin "1") (pinfunction "1_1") (pintype "passive"))
    )
    (net (code "46") (name "Net-(IC1B--IN)") (class "Default")
      (node (ref "IC1") (pin "6") (pinfunction "-IN_6") (pintype "input"))
      (node (ref "IC1") (pin "7") (pinfunction "OUT_7") (pintype "output"))
      (node (ref "R5") (pin "1") (pinfunction "1_1") (pintype "passive"))
    )
    (net (code "47") (name "Net-(IC1C-+IN)") (class "Default")
      (node (ref "IC1") (pin "10") (pinfunction "+IN_10") (pintype "input"))
      (node (ref "R5") (pin "2") (pinfunction "2_2") (pintype "passive"))
      (node (ref "R6") (pin "2") (pinfunction "2_2") (pintype "passive"))
    )
    (net (code "48") (name "Net-(IC1C--IN)") (class "Default")
      (node (ref "IC1") (pin "9") (pinfunction "-IN_9") (pintype "input"))
      (node (ref "R3") (pin "2") (pinfunction "2_2") (pintype "passive"))
      (node (ref "R4") (pin "1") (pinfunction "1_1") (pintype "passive"))
    )
    (net (code "49") (name "Net-(IC1C-OUT)") (class "Default")
      (node (ref "IC1") (pin "8") (pinfunction "OUT_8") (pintype "output"))
      (node (ref "R4") (pin "2") (pinfunction "2_2") (pintype "passive"))
      (node (ref "R8") (pin "1") (pinfunction "1_1") (pintype "passive"))
    )
    (net (code "50") (name "Net-(IC4-VIN)") (class "Default")
      (node (ref "IC3") (pin "OUT") (pinfunction "OUT_OUT") (pintype "output"))
      (node (ref "IC4") (pin "3") (pinfunction "VIN_3") (pintype "input"))
    )
    (net (code "51") (name "Net-(OK7-A)") (class "Default")
      (node (ref "OK7") (pin "1") (pinfunction "A_1") (pintype "passive"))
      (node (ref "R18") (pin "1") (pinfunction "1_1") (pintype "passive"))
    )
    (net (code "52") (name "Net-(OK7-C)") (class "Default")
      (node (ref "B3") (pin "-") (pinfunction "-_-") (pintype "passive"))
      (node (ref "OK7") (pin "2") (pinfunction "C_2") (pintype "passive"))
    )
    (net (code "53") (name "Net-(R14-Pad2)") (class "Default")
      (node (ref "R14") (pin "2") (pinfunction "2_2") (pintype "passive"))
      (node (ref "SG1") (pin "-") (pinfunction "-_-") (pintype "passive"))
    )
    (net (code "54") (name "Net-(U$1-PB6(XTAL1{slash}TOSC1))") (class "Default")
      (node (ref "C2") (pin "2") (pinfunction "2_2") (pintype "passive"))
      (node (ref "Q2") (pin "2") (pinfunction "2_2") (pintype "passive"))
      (node (ref "U$1") (pin "9") (pinfunction "PB6(XTAL1/TOSC1)_9") (pintype "bidirectional"))
    )
    (net (code "55") (name "Net-(U$1-PB7(XTAL2{slash}TOSC2))") (class "Default")
      (node (ref "C8") (pin "2") (pinfunction "2_2") (pintype "passive"))
      (node (ref "Q2") (pin "1") (pinfunction "1_1") (pintype "passive"))
      (node (ref "U$1") (pin "10") (pinfunction "PB7(XTAL2/TOSC2)_10") (pintype "bidirectional"))
    )
    (net (code "56") (name "OUT_PUMP") (class "Default")
      (node (ref "K1") (pin "NO") (pinfunction "NO_NO") (pintype "bidirectional"))
      (node (ref "X6") (pin "1") (pinfunction "KL_1") (pintype "passive"))
    )
    (net (code "57") (name "OUT_S1_GAS") (class "Default")
      (node (ref "U$4") (pin "SWOPEN") (pinfunction "SWOPEN_SWOPEN") (pintype "bidirectional"))
      (node (ref "X2") (pin "1") (pinfunction "KL_1") (pintype "passive"))
    )
    (net (code "58") (name "OUT_S2_WAT") (class "Default")
      (node (ref "U$5") (pin "SWOPEN") (pinfunction "SWOPEN_SWOPEN") (pintype "bidirectional"))
      (node (ref "X3") (pin "1") (pinfunction "KL_1") (pintype "passive"))
    )
    (net (code "59") (name "OUT_S3_VAP") (class "Default")
      (node (ref "U$6") (pin "SWOPEN") (pinfunction "SWOPEN_SWOPEN") (pintype "bidirectional"))
      (node (ref "X4") (pin "1") (pinfunction "KL_1") (pintype "passive"))
    )
    (net (code "60") (name "OUT_S4_DRY") (class "Default")
      (node (ref "X5") (pin "1") (pinfunction "KL_1") (pintype "passive"))
    )
    (net (code "61") (name "OUT_S4_VAP") (class "Default")
      (node (ref "U$7") (pin "SWOPEN") (pinfunction "SWOPEN_SWOPEN") (pintype "bidirectional"))
    )
    (net (code "62") (name "RS") (class "Default")
      (node (ref "JP1") (pin "4") (pinfunction "4_4") (pintype "passive"))
      (node (ref "V1") (pin "7") (pinfunction "QH_7") (pintype "tri_state"))
    )
    (net (code "63") (name "RTE+") (class "Default")
      (node (ref "C9") (pin "+") (pinfunction "+_+") (pintype "passive"))
      (node (ref "IC1") (pin "5") (pinfunction "+IN_5") (pintype "input"))
      (node (ref "R12") (pin "2") (pinfunction "2_2") (pintype "passive"))
      (node (ref "X8") (pin "1") (pinfunction "KL_1") (pintype "passive"))
    )
    (net (code "64") (name "SH1_BUZZER") (class "Default")
      (node (ref "SG1") (pin "+") (pinfunction "+_+") (pintype "passive"))
      (node (ref "V2") (pin "1") (pinfunction "QB_1") (pintype "tri_state"))
    )
    (net (code "65") (name "SH3_EN_PUMP") (class "Default")
      (node (ref "IC5") (pin "1") (pinfunction "I1_1") (pintype "input"))
      (node (ref "V2") (pin "3") (pinfunction "QD_3") (pintype "tri_state"))
    )
    (net (code "66") (name "SH4_EN_S3_VAP") (class "Default")
      (node (ref "IC5") (pin "2") (pinfunction "I2_2") (pintype "input"))
      (node (ref "V2") (pin "4") (pinfunction "QE_4") (pintype "tri_state"))
    )
    (net (code "67") (name "SH5_EN_S2_WAT") (class "Default")
      (node (ref "IC5") (pin "3") (pinfunction "I3_3") (pintype "input"))
      (node (ref "V2") (pin "5") (pinfunction "QF_5") (pintype "tri_state"))
    )
    (net (code "68") (name "SH6_EN_S4_DRY") (class "Default")
      (node (ref "IC5") (pin "4") (pinfunction "I4_4") (pintype "input"))
      (node (ref "V2") (pin "6") (pinfunction "QG_6") (pintype "tri_state"))
    )
    (net (code "69") (name "SH7_EN_S1_GAS") (class "Default")
      (node (ref "IC5") (pin "5") (pinfunction "I5_5") (pintype "input"))
      (node (ref "V2") (pin "7") (pinfunction "QH_7") (pintype "tri_state"))
    )
    (net (code "70") (name "ULN_EN_R_PUMP") (class "Default")
      (node (ref "D1") (pin "K") (pinfunction "C_K") (pintype "passive"))
      (node (ref "IC5") (pin "16") (pinfunction "O1_16") (pintype "open_collector"))
      (node (ref "K1") (pin "COIL2") (pinfunction "COIL2_COIL2") (pintype "bidirectional"))
    )
    (net (code "71") (name "ULN_EN_R_S1_GAS") (class "Default")
      (node (ref "D2") (pin "K") (pinfunction "C_K") (pintype "passive"))
      (node (ref "IC5") (pin "12") (pinfunction "O5_12") (pintype "open_collector"))
      (node (ref "U$4") (pin "COIL0") (pinfunction "COIL0_COIL0") (pintype "bidirectional"))
    )
    (net (code "72") (name "ULN_EN_R_S2_WAT") (class "Default")
      (node (ref "D3") (pin "K") (pinfunction "C_K") (pintype "passive"))
      (node (ref "IC5") (pin "14") (pinfunction "O3_14") (pintype "open_collector"))
      (node (ref "U$5") (pin "COIL0") (pinfunction "COIL0_COIL0") (pintype "bidirectional"))
    )
    (net (code "73") (name "ULN_EN_R_S3_VAP") (class "Default")
      (node (ref "D4") (pin "K") (pinfunction "C_K") (pintype "passive"))
      (node (ref "IC5") (pin "15") (pinfunction "O2_15") (pintype "open_collector"))
      (node (ref "U$6") (pin "COIL0") (pinfunction "COIL0_COIL0") (pintype "bidirectional"))
    )
    (net (code "74") (name "ULN_EN_R_S4_DRY") (class "Default")
      (node (ref "D5") (pin "K") (pinfunction "C_K") (pintype "passive"))
      (node (ref "IC5") (pin "13") (pinfunction "O4_13") (pintype "open_collector"))
      (node (ref "U$7") (pin "COIL0") (pinfunction "COIL0_COIL0") (pintype "bidirectional"))
    )
    (net (code "75") (name "UNO_REST") (class "Default")
      (node (ref "R1") (pin "1") (pinfunction "1_1") (pintype "passive"))
      (node (ref "U$1") (pin "1") (pinfunction "PC6(/RESET)_1") (pintype "bidirectional"))
      (node (ref "U$3") (pin "C1") (pinfunction "GPIO0_C1") (pintype "bidirectional"))
    )
    (net (code "76") (name "VEE") (class "Default")
      (node (ref "C11") (pin "2") (pinfunction "2_2") (pintype "passive"))
      (node (ref "C4") (pin "+") (pinfunction "+_+") (pintype "passive"))
      (node (ref "JP1") (pin "3") (pinfunction "3_3") (pintype "passive"))
      (node (ref "R11") (pin "1") (pinfunction "1_1") (pintype "passive"))
    )
    (net (code "77") (name "VIN") (class "Default")
      (node (ref "B2") (pin "+") (pinfunction "+_+") (pintype "passive"))
      (node (ref "C22") (pin "+") (pinfunction "+_+") (pintype "passive"))
      (node (ref "C23") (pin "2") (pinfunction "2_2") (pintype "passive"))
      (node (ref "IC2") (pin "IN") (pinfunction "IN_IN") (pintype "input"))
      (node (ref "IC3") (pin "IN") (pinfunction "IN_IN") (pintype "input"))
      (node (ref "IC5") (pin "9") (pinfunction "CD+_9") (pintype "passive"))
      (node (ref "K1") (pin "COIL1") (pinfunction "COIL1_COIL1") (pintype "bidirectional"))
      (node (ref "R20") (pin "2") (pinfunction "2_2") (pintype "passive"))
      (node (ref "R21") (pin "2") (pinfunction "2_2") (pintype "passive"))
      (node (ref "R25") (pin "2") (pinfunction "2_2") (pintype "passive"))
      (node (ref "R42") (pin "2") (pinfunction "2_2") (pintype "passive"))
      (node (ref "R7") (pin "2") (pinfunction "2_2") (pintype "passive"))
      (node (ref "R9") (pin "2") (pinfunction "2_2") (pintype "passive"))
      (node (ref "U$4") (pin "COIL1") (pinfunction "COIL1_COIL1") (pintype "bidirectional"))
      (node (ref "U$5") (pin "COIL1") (pinfunction "COIL1_COIL1") (pintype "bidirectional"))
      (node (ref "U$6") (pin "COIL1") (pinfunction "COIL1_COIL1") (pintype "bidirectional"))
      (node (ref "U$7") (pin "COIL1") (pinfunction "COIL1_COIL1") (pintype "bidirectional"))
    )
    (net (code "78") (name "WIFI_LED") (class "Default")
      (node (ref "U$3") (pin "B1") (pinfunction "GPIO2_B1") (pintype "bidirectional"))
    )
    (net (code "79") (name "unconnected-(IC5-I6-Pad6)") (class "Default")
      (node (ref "IC5") (pin "6") (pinfunction "I6_6") (pintype "input"))
    )
    (net (code "80") (name "unconnected-(IC5-I7-Pad7)") (class "Default")
      (node (ref "IC5") (pin "7") (pinfunction "I7_7") (pintype "input"))
    )
    (net (code "81") (name "unconnected-(IC5-O6-Pad11)") (class "Default")
      (node (ref "IC5") (pin "11") (pinfunction "O6_11") (pintype "open_collector"))
    )
    (net (code "82") (name "unconnected-(IC5-O7-Pad10)") (class "Default")
      (node (ref "IC5") (pin "10") (pinfunction "O7_10") (pintype "open_collector"))
    )
    (net (code "83") (name "unconnected-(K1-PadNC)") (class "Default")
      (node (ref "K1") (pin "NC") (pinfunction "NC_NC") (pintype "bidirectional"))
    )
    (net (code "84") (name "unconnected-(U$1-AREF-Pad21)") (class "Default")
      (node (ref "U$1") (pin "21") (pinfunction "AREF_21") (pintype "bidirectional"))
    )
    (net (code "85") (name "unconnected-(U$3-RST-PadC2)") (class "Default")
      (node (ref "U$3") (pin "C2") (pinfunction "RST_C2") (pintype "bidirectional"))
    )
    (net (code "86") (name "unconnected-(U$4-SWCLOSE-PadSWCLOSED)") (class "Default")
      (node (ref "U$4") (pin "SWCLOSED") (pinfunction "SWCLOSE_SWCLOSED") (pintype "bidirectional"))
    )
    (net (code "87") (name "unconnected-(U$5-SWCLOSE-PadSWCLOSED)") (class "Default")
      (node (ref "U$5") (pin "SWCLOSED") (pinfunction "SWCLOSE_SWCLOSED") (pintype "bidirectional"))
    )
    (net (code "88") (name "unconnected-(U$6-SWCLOSE-PadSWCLOSED)") (class "Default")
      (node (ref "U$6") (pin "SWCLOSED") (pinfunction "SWCLOSE_SWCLOSED") (pintype "bidirectional"))
    )
    (net (code "89") (name "unconnected-(U$7-SWCLOSE-PadSWCLOSED)") (class "Default")
      (node (ref "U$7") (pin "SWCLOSED") (pinfunction "SWCLOSE_SWCLOSED") (pintype "bidirectional"))
    )
    (net (code "90") (name "unconnected-(V1C-QE-Pad4)") (class "Default")
      (node (ref "V1") (pin "4") (pinfunction "QE_4") (pintype "tri_state"))
    )
    (net (code "91") (name "unconnected-(V1C-QF-Pad5)") (class "Default")
      (node (ref "V1") (pin "5") (pinfunction "QF_5") (pintype "tri_state"))
    )
    (net (code "92") (name "unconnected-(V1C-QH*-Pad9)") (class "Default")
      (node (ref "V1") (pin "9") (pinfunction "QH*_9") (pintype "output"))
    )
    (net (code "93") (name "unconnected-(V2C-QA-Pad15)") (class "Default")
      (node (ref "V2") (pin "15") (pinfunction "QA_15") (pintype "tri_state"))
    )
    (net (code "94") (name "unconnected-(V2C-QH*-Pad9)") (class "Default")
      (node (ref "V2") (pin "9") (pinfunction "QH*_9") (pintype "output"))
    )
  )
)
